# T7BR-Schematic.net
KiCad netlist of a schematic drawn in Altium Designer
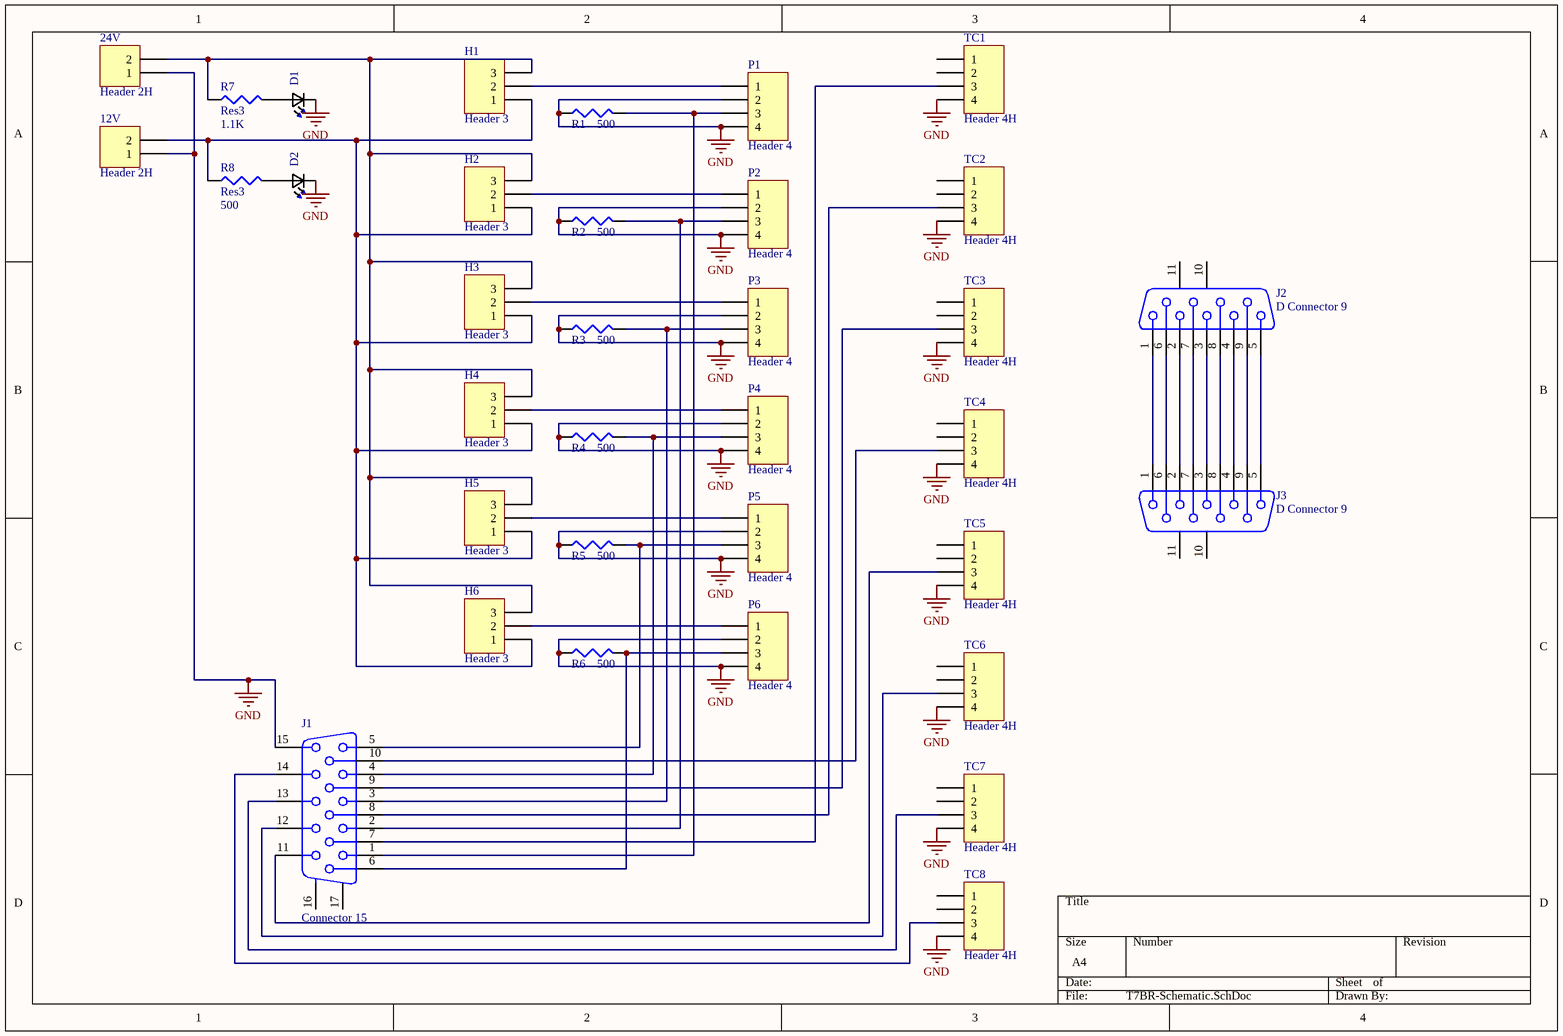
[diagram p0: T7BR-Schematic.SchDoc]

(export (version "E")
  (design (tool "Eeschema 10.0.6"))
  (components
    (comp (ref "12V")
      (value "Header 2H")
      (footprint "WM4900-ND")
      (description "Header, 2-Pin, Right Angle")
      (fields (field (name "PUBLISHER") "Altium Limited"))
      (libsource (lib "Miscellaneous Connectors") (part "Header 2H"))
    )
    (comp (ref "24V")
      (value "Header 2H")
      (footprint "WM4900-ND")
      (description "Header, 2-Pin, Right Angle")
      (fields (field (name "PUBLISHER") "Altium Limited"))
      (libsource (lib "Miscellaneous Connectors") (part "Header 2H"))
    )
    (comp (ref "D1")
      (value "~")
      (footprint "*0603")
      (description "Green 571nm LED Indication - Discrete 2V 0603 _1608 Metric_")
      (fields (field (name "DIGI-KEY_PART_NUMBER") "160-1446-1-ND") (field (name "MP") "LTST-C191KGKT"))
      (libsource (lib "LTST-C191KGKT") (part "LTST-C191KGKT"))
    )
    (comp (ref "D2")
      (value "~")
      (footprint "*0603")
      (description "Green 571nm LED Indication - Discrete 2V 0603 _1608 Metric_")
      (fields (field (name "DIGI-KEY_PART_NUMBER") "160-1446-1-ND") (field (name "MP") "LTST-C191KGKT"))
      (libsource (lib "LTST-C191KGKT") (part "LTST-C191KGKT"))
    )
    (comp (ref "H1")
      (value "Header 3")
      (footprint "HDR1X3")
      (description "Header, 3-Pin")
      (fields (field (name "PUBLISHER") "Altium Limited"))
      (libsource (lib "Miscellaneous Connectors") (part "Header 3"))
    )
    (comp (ref "H2")
      (value "Header 3")
      (footprint "HDR1X3")
      (description "Header, 3-Pin")
      (fields (field (name "PUBLISHER") "Altium Limited"))
      (libsource (lib "Miscellaneous Connectors") (part "Header 3"))
    )
    (comp (ref "H3")
      (value "Header 3")
      (footprint "HDR1X3")
      (description "Header, 3-Pin")
      (fields (field (name "PUBLISHER") "Altium Limited"))
      (libsource (lib "Miscellaneous Connectors") (part "Header 3"))
    )
    (comp (ref "H4")
      (value "Header 3")
      (footprint "HDR1X3")
      (description "Header, 3-Pin")
      (fields (field (name "PUBLISHER") "Altium Limited"))
      (libsource (lib "Miscellaneous Connectors") (part "Header 3"))
    )
    (comp (ref "H5")
      (value "Header 3")
      (footprint "HDR1X3")
      (description "Header, 3-Pin")
      (fields (field (name "PUBLISHER") "Altium Limited"))
      (libsource (lib "Miscellaneous Connectors") (part "Header 3"))
    )
    (comp (ref "H6")
      (value "Header 3")
      (footprint "HDR1X3")
      (description "Header, 3-Pin")
      (fields (field (name "PUBLISHER") "Altium Limited"))
      (libsource (lib "Miscellaneous Connectors") (part "Header 3"))
    )
    (comp (ref "J1")
      (value "Connector 15")
      (footprint "DSUB_15")
      (description "Receptacle Assembly, 15-Pin, Sim Line Connector")
      (fields (field (name "PUBLISHER") "Altium Limited"))
      (libsource (lib "Miscellaneous Connectors") (part "Connector 15"))
    )
    (comp (ref "J2")
      (value "D Connector 9")
      (footprint "DSUB_9")
      (description "Receptacle Assembly, 9 Position, Right Angle")
      (fields (field (name "PUBLISHER") "Altium Limited"))
      (libsource (lib "Miscellaneous Connectors") (part "D Connector 9"))
    )
    (comp (ref "J3")
      (value "D Connector 9")
      (footprint "DSUB_9")
      (description "Receptacle Assembly, 9 Position, Right Angle")
      (fields (field (name "PUBLISHER") "Altium Limited"))
      (libsource (lib "") (part "D Connector 9_1"))
    )
    (comp (ref "P1")
      (value "Header 4")
      (footprint "WM4900-ND-4")
      (description "Header, 4-Pin")
      (fields (field (name "PUBLISHER") "Altium Limited"))
      (libsource (lib "Miscellaneous Connectors") (part "Header 4"))
    )
    (comp (ref "P2")
      (value "Header 4")
      (footprint "WM4900-ND-4")
      (description "Header, 4-Pin")
      (fields (field (name "PUBLISHER") "Altium Limited"))
      (libsource (lib "Miscellaneous Connectors") (part "Header 4"))
    )
    (comp (ref "P3")
      (value "Header 4")
      (footprint "WM4900-ND-4")
      (description "Header, 4-Pin")
      (fields (field (name "PUBLISHER") "Altium Limited"))
      (libsource (lib "Miscellaneous Connectors") (part "Header 4"))
    )
    (comp (ref "P4")
      (value "Header 4")
      (footprint "WM4900-ND-4")
      (description "Header, 4-Pin")
      (fields (field (name "PUBLISHER") "Altium Limited"))
      (libsource (lib "Miscellaneous Connectors") (part "Header 4"))
    )
    (comp (ref "P5")
      (value "Header 4")
      (footprint "WM4900-ND-4")
      (description "Header, 4-Pin")
      (fields (field (name "PUBLISHER") "Altium Limited"))
      (libsource (lib "Miscellaneous Connectors") (part "Header 4"))
    )
    (comp (ref "P6")
      (value "Header 4")
      (footprint "WM4900-ND-4")
      (description "Header, 4-Pin")
      (fields (field (name "PUBLISHER") "Altium Limited"))
      (libsource (lib "Miscellaneous Connectors") (part "Header 4"))
    )
    (comp (ref "R1")
      (value "500")
      (footprint "J1-0603")
      (description "Resistor")
      (fields (field (name "PUBLISHER") "Altium Limited"))
      (libsource (lib "Miscellaneous Devices") (part "Res3"))
    )
    (comp (ref "R2")
      (value "500")
      (footprint "J1-0603")
      (description "Resistor")
      (fields (field (name "PUBLISHER") "Altium Limited"))
      (libsource (lib "Miscellaneous Devices") (part "Res3"))
    )
    (comp (ref "R3")
      (value "500")
      (footprint "J1-0603")
      (description "Resistor")
      (fields (field (name "PUBLISHER") "Altium Limited"))
      (libsource (lib "Miscellaneous Devices") (part "Res3"))
    )
    (comp (ref "R4")
      (value "500")
      (footprint "J1-0603")
      (description "Resistor")
      (fields (field (name "PUBLISHER") "Altium Limited"))
      (libsource (lib "Miscellaneous Devices") (part "Res3"))
    )
    (comp (ref "R5")
      (value "500")
      (footprint "J1-0603")
      (description "Resistor")
      (fields (field (name "PUBLISHER") "Altium Limited"))
      (libsource (lib "Miscellaneous Devices") (part "Res3"))
    )
    (comp (ref "R6")
      (value "500")
      (footprint "J1-0603")
      (description "Resistor")
      (fields (field (name "PUBLISHER") "Altium Limited"))
      (libsource (lib "Miscellaneous Devices") (part "Res3"))
    )
    (comp (ref "R7")
      (value "Res3")
      (footprint "J1-0603")
      (description "Resistor")
      (fields (field (name "ALTIUM_VALUE") "1.1K") (field (name "PUBLISHER") "Altium Limited"))
      (libsource (lib "Miscellaneous Devices") (part "Res3"))
    )
    (comp (ref "R8")
      (value "Res3")
      (footprint "J1-0603")
      (description "Resistor")
      (fields (field (name "ALTIUM_VALUE") "500") (field (name "PUBLISHER") "Altium Limited"))
      (libsource (lib "Miscellaneous Devices") (part "Res3"))
    )
    (comp (ref "TC1")
      (value "Header 4H")
      (footprint "Thermocouple F")
      (description "Header, 4-Pin, Right Angle")
      (fields (field (name "PUBLISHER") "Altium Limited"))
      (libsource (lib "Miscellaneous Connectors") (part "Header 4H"))
    )
    (comp (ref "TC2")
      (value "Header 4H")
      (footprint "Thermocouple F")
      (description "Header, 4-Pin, Right Angle")
      (fields (field (name "PUBLISHER") "Altium Limited"))
      (libsource (lib "Miscellaneous Connectors") (part "Header 4H"))
    )
    (comp (ref "TC3")
      (value "Header 4H")
      (footprint "Thermocouple F")
      (description "Header, 4-Pin, Right Angle")
      (fields (field (name "PUBLISHER") "Altium Limited"))
      (libsource (lib "Miscellaneous Connectors") (part "Header 4H"))
    )
    (comp (ref "TC4")
      (value "Header 4H")
      (footprint "Thermocouple F")
      (description "Header, 4-Pin, Right Angle")
      (fields (field (name "PUBLISHER") "Altium Limited"))
      (libsource (lib "Miscellaneous Connectors") (part "Header 4H"))
    )
    (comp (ref "TC5")
      (value "Header 4H")
      (footprint "Thermocouple F")
      (description "Header, 4-Pin, Right Angle")
      (fields (field (name "PUBLISHER") "Altium Limited"))
      (libsource (lib "Miscellaneous Connectors") (part "Header 4H"))
    )
    (comp (ref "TC6")
      (value "Header 4H")
      (footprint "Thermocouple F")
      (description "Header, 4-Pin, Right Angle")
      (fields (field (name "PUBLISHER") "Altium Limited"))
      (libsource (lib "Miscellaneous Connectors") (part "Header 4H"))
    )
    (comp (ref "TC7")
      (value "Header 4H")
      (footprint "Thermocouple F")
      (description "Header, 4-Pin, Right Angle")
      (fields (field (name "PUBLISHER") "Altium Limited"))
      (libsource (lib "Miscellaneous Connectors") (part "Header 4H"))
    )
    (comp (ref "TC8")
      (value "Header 4H")
      (footprint "Thermocouple F")
      (description "Header, 4-Pin, Right Angle")
      (fields (field (name "PUBLISHER") "Altium Limited"))
      (libsource (lib "Miscellaneous Connectors") (part "Header 4H"))
    )
  )
  (nets
    (net (code "1") (name "GND") (class "Default")
      (node (ref "12V") (pin "1") (pinfunction "1_1") (pintype "passive"))
      (node (ref "24V") (pin "1") (pinfunction "1_1") (pintype "passive"))
      (node (ref "D1") (pin "1") (pinfunction "K2_1") (pintype "passive"))
      (node (ref "D2") (pin "1") (pinfunction "K2_1") (pintype "passive"))
      (node (ref "J1") (pin "15") (pinfunction "15_15") (pintype "passive"))
      (node (ref "P1") (pin "2") (pinfunction "2_2") (pintype "passive"))
      (node (ref "P1") (pin "4") (pinfunction "4_4") (pintype "passive"))
      (node (ref "P2") (pin "2") (pinfunction "2_2") (pintype "passive"))
      (node (ref "P2") (pin "4") (pinfunction "4_4") (pintype "passive"))
      (node (ref "P3") (pin "2") (pinfunction "2_2") (pintype "passive"))
      (node (ref "P3") (pin "4") (pinfunction "4_4") (pintype "passive"))
      (node (ref "P4") (pin "2") (pinfunction "2_2") (pintype "passive"))
      (node (ref "P4") (pin "4") (pinfunction "4_4") (pintype "passive"))
      (node (ref "P5") (pin "2") (pinfunction "2_2") (pintype "passive"))
      (node (ref "P5") (pin "4") (pinfunction "4_4") (pintype "passive"))
      (node (ref "P6") (pin "2") (pinfunction "2_2") (pintype "passive"))
      (node (ref "P6") (pin "4") (pinfunction "4_4") (pintype "passive"))
      (node (ref "R1") (pin "1") (pinfunction "1_1") (pintype "passive"))
      (node (ref "R2") (pin "1") (pinfunction "1_1") (pintype "passive"))
      (node (ref "R3") (pin "1") (pinfunction "1_1") (pintype "passive"))
      (node (ref "R4") (pin "1") (pinfunction "1_1") (pintype "passive"))
      (node (ref "R5") (pin "1") (pinfunction "1_1") (pintype "passive"))
      (node (ref "R6") (pin "1") (pinfunction "1_1") (pintype "passive"))
      (node (ref "TC1") (pin "4") (pinfunction "4_4") (pintype "passive"))
      (node (ref "TC2") (pin "4") (pinfunction "4_4") (pintype "passive"))
      (node (ref "TC3") (pin "4") (pinfunction "4_4") (pintype "passive"))
      (node (ref "TC4") (pin "4") (pinfunction "4_4") (pintype "passive"))
      (node (ref "TC5") (pin "4") (pinfunction "4_4") (pintype "passive"))
      (node (ref "TC6") (pin "4") (pinfunction "4_4") (pintype "passive"))
      (node (ref "TC7") (pin "4") (pinfunction "4_4") (pintype "passive"))
      (node (ref "TC8") (pin "4") (pinfunction "4_4") (pintype "passive"))
    )
    (net (code "2") (name "Net-(12V-Pad2)") (class "Default")
      (node (ref "12V") (pin "2") (pinfunction "2_2") (pintype "passive"))
      (node (ref "H1") (pin "1") (pinfunction "1_1") (pintype "passive"))
      (node (ref "H2") (pin "1") (pinfunction "1_1") (pintype "passive"))
      (node (ref "H3") (pin "1") (pinfunction "1_1") (pintype "passive"))
      (node (ref "H4") (pin "1") (pinfunction "1_1") (pintype "passive"))
      (node (ref "H5") (pin "1") (pinfunction "1_1") (pintype "passive"))
      (node (ref "H6") (pin "1") (pinfunction "1_1") (pintype "passive"))
      (node (ref "R8") (pin "1") (pinfunction "1_1") (pintype "passive"))
    )
    (net (code "3") (name "Net-(24V-Pad2)") (class "Default")
      (node (ref "24V") (pin "2") (pinfunction "2_2") (pintype "passive"))
      (node (ref "H1") (pin "3") (pinfunction "3_3") (pintype "passive"))
      (node (ref "H2") (pin "3") (pinfunction "3_3") (pintype "passive"))
      (node (ref "H3") (pin "3") (pinfunction "3_3") (pintype "passive"))
      (node (ref "H4") (pin "3") (pinfunction "3_3") (pintype "passive"))
      (node (ref "H5") (pin "3") (pinfunction "3_3") (pintype "passive"))
      (node (ref "H6") (pin "3") (pinfunction "3_3") (pintype "passive"))
      (node (ref "R7") (pin "1") (pinfunction "1_1") (pintype "passive"))
    )
    (net (code "4") (name "Net-(D1-A2)") (class "Default")
      (node (ref "D1") (pin "2") (pinfunction "A2_2") (pintype "passive"))
      (node (ref "R7") (pin "2") (pinfunction "2_2") (pintype "passive"))
    )
    (net (code "5") (name "Net-(D2-A2)") (class "Default")
      (node (ref "D2") (pin "2") (pinfunction "A2_2") (pintype "passive"))
      (node (ref "R8") (pin "2") (pinfunction "2_2") (pintype "passive"))
    )
    (net (code "6") (name "Net-(H1-Pad2)") (class "Default")
      (node (ref "H1") (pin "2") (pinfunction "2_2") (pintype "passive"))
      (node (ref "P1") (pin "1") (pinfunction "1_1") (pintype "passive"))
    )
    (net (code "7") (name "Net-(H2-Pad2)") (class "Default")
      (node (ref "H2") (pin "2") (pinfunction "2_2") (pintype "passive"))
      (node (ref "P2") (pin "1") (pinfunction "1_1") (pintype "passive"))
    )
    (net (code "8") (name "Net-(H3-Pad2)") (class "Default")
      (node (ref "H3") (pin "2") (pinfunction "2_2") (pintype "passive"))
      (node (ref "P3") (pin "1") (pinfunction "1_1") (pintype "passive"))
    )
    (net (code "9") (name "Net-(H4-Pad2)") (class "Default")
      (node (ref "H4") (pin "2") (pinfunction "2_2") (pintype "passive"))
      (node (ref "P4") (pin "1") (pinfunction "1_1") (pintype "passive"))
    )
    (net (code "10") (name "Net-(H5-Pad2)") (class "Default")
      (node (ref "H5") (pin "2") (pinfunction "2_2") (pintype "passive"))
      (node (ref "P5") (pin "1") (pinfunction "1_1") (pintype "passive"))
    )
    (net (code "11") (name "Net-(H6-Pad2)") (class "Default")
      (node (ref "H6") (pin "2") (pinfunction "2_2") (pintype "passive"))
      (node (ref "P6") (pin "1") (pinfunction "1_1") (pintype "passive"))
    )
    (net (code "12") (name "Net-(J1-Pad1)") (class "Default")
      (node (ref "J1") (pin "1") (pinfunction "1_1") (pintype "passive"))
      (node (ref "P1") (pin "3") (pinfunction "3_3") (pintype "passive"))
      (node (ref "R1") (pin "2") (pinfunction "2_2") (pintype "passive"))
    )
    (net (code "13") (name "Net-(J1-Pad2)") (class "Default")
      (node (ref "J1") (pin "2") (pinfunction "2_2") (pintype "passive"))
      (node (ref "P2") (pin "3") (pinfunction "3_3") (pintype "passive"))
      (node (ref "R2") (pin "2") (pinfunction "2_2") (pintype "passive"))
    )
    (net (code "14") (name "Net-(J1-Pad3)") (class "Default")
      (node (ref "J1") (pin "3") (pinfunction "3_3") (pintype "passive"))
      (node (ref "P3") (pin "3") (pinfunction "3_3") (pintype "passive"))
      (node (ref "R3") (pin "2") (pinfunction "2_2") (pintype "passive"))
    )
    (net (code "15") (name "Net-(J1-Pad4)") (class "Default")
      (node (ref "J1") (pin "4") (pinfunction "4_4") (pintype "passive"))
      (node (ref "P4") (pin "3") (pinfunction "3_3") (pintype "passive"))
      (node (ref "R4") (pin "2") (pinfunction "2_2") (pintype "passive"))
    )
    (net (code "16") (name "Net-(J1-Pad5)") (class "Default")
      (node (ref "J1") (pin "5") (pinfunction "5_5") (pintype "passive"))
      (node (ref "P5") (pin "3") (pinfunction "3_3") (pintype "passive"))
      (node (ref "R5") (pin "2") (pinfunction "2_2") (pintype "passive"))
    )
    (net (code "17") (name "Net-(J1-Pad6)") (class "Default")
      (node (ref "J1") (pin "6") (pinfunction "6_6") (pintype "passive"))
      (node (ref "P6") (pin "3") (pinfunction "3_3") (pintype "passive"))
      (node (ref "R6") (pin "2") (pinfunction "2_2") (pintype "passive"))
    )
    (net (code "18") (name "Net-(J1-Pad7)") (class "Default")
      (node (ref "J1") (pin "7") (pinfunction "7_7") (pintype "passive"))
      (node (ref "TC1") (pin "3") (pinfunction "3_3") (pintype "passive"))
    )
    (net (code "19") (name "Net-(J1-Pad8)") (class "Default")
      (node (ref "J1") (pin "8") (pinfunction "8_8") (pintype "passive"))
      (node (ref "TC2") (pin "3") (pinfunction "3_3") (pintype "passive"))
    )
    (net (code "20") (name "Net-(J1-Pad9)") (class "Default")
      (node (ref "J1") (pin "9") (pinfunction "9_9") (pintype "passive"))
      (node (ref "TC3") (pin "3") (pinfunction "3_3") (pintype "passive"))
    )
    (net (code "21") (name "Net-(J1-Pad10)") (class "Default")
      (node (ref "J1") (pin "10") (pinfunction "10_10") (pintype "passive"))
      (node (ref "TC4") (pin "3") (pinfunction "3_3") (pintype "passive"))
    )
    (net (code "22") (name "Net-(J1-Pad11)") (class "Default")
      (node (ref "J1") (pin "11") (pinfunction "11_11") (pintype "passive"))
      (node (ref "TC5") (pin "3") (pinfunction "3_3") (pintype "passive"))
    )
    (net (code "23") (name "Net-(J1-Pad12)") (class "Default")
      (node (ref "J1") (pin "12") (pinfunction "12_12") (pintype "passive"))
      (node (ref "TC6") (pin "3") (pinfunction "3_3") (pintype "passive"))
    )
    (net (code "24") (name "Net-(J1-Pad13)") (class "Default")
      (node (ref "J1") (pin "13") (pinfunction "13_13") (pintype "passive"))
      (node (ref "TC7") (pin "3") (pinfunction "3_3") (pintype "passive"))
    )
    (net (code "25") (name "Net-(J1-Pad14)") (class "Default")
      (node (ref "J1") (pin "14") (pinfunction "14_14") (pintype "passive"))
      (node (ref "TC8") (pin "3") (pinfunction "3_3") (pintype "passive"))
    )
    (net (code "26") (name "Net-(J2-Pad1)") (class "Default")
      (node (ref "J2") (pin "1") (pinfunction "1_1") (pintype "passive"))
      (node (ref "J3") (pin "1") (pinfunction "1_1") (pintype "passive"))
    )
    (net (code "27") (name "Net-(J2-Pad2)") (class "Default")
      (node (ref "J2") (pin "2") (pinfunction "2_2") (pintype "passive"))
      (node (ref "J3") (pin "2") (pinfunction "2_2") (pintype "passive"))
    )
    (net (code "28") (name "Net-(J2-Pad3)") (class "Default")
      (node (ref "J2") (pin "3") (pinfunction "3_3") (pintype "passive"))
      (node (ref "J3") (pin "3") (pinfunction "3_3") (pintype "passive"))
    )
    (net (code "29") (name "Net-(J2-Pad4)") (class "Default")
      (node (ref "J2") (pin "4") (pinfunction "4_4") (pintype "passive"))
      (node (ref "J3") (pin "4") (pinfunction "4_4") (pintype "passive"))
    )
    (net (code "30") (name "Net-(J2-Pad5)") (class "Default")
      (node (ref "J2") (pin "5") (pinfunction "5_5") (pintype "passive"))
      (node (ref "J3") (pin "5") (pinfunction "5_5") (pintype "passive"))
    )
    (net (code "31") (name "Net-(J2-Pad6)") (class "Default")
      (node (ref "J2") (pin "6") (pinfunction "6_6") (pintype "passive"))
      (node (ref "J3") (pin "6") (pinfunction "6_6") (pintype "passive"))
    )
    (net (code "32") (name "Net-(J2-Pad7)") (class "Default")
      (node (ref "J2") (pin "7") (pinfunction "7_7") (pintype "passive"))
      (node (ref "J3") (pin "7") (pinfunction "7_7") (pintype "passive"))
    )
    (net (code "33") (name "Net-(J2-Pad8)") (class "Default")
      (node (ref "J2") (pin "8") (pinfunction "8_8") (pintype "passive"))
      (node (ref "J3") (pin "8") (pinfunction "8_8") (pintype "passive"))
    )
    (net (code "34") (name "Net-(J2-Pad9)") (class "Default")
      (node (ref "J2") (pin "9") (pinfunction "9_9") (pintype "passive"))
      (node (ref "J3") (pin "9") (pinfunction "9_9") (pintype "passive"))
    )
    (net (code "35") (name "unconnected-(J1-MH1-Pad16)") (class "Default")
      (node (ref "J1") (pin "16") (pinfunction "MH1_16") (pintype "passive"))
    )
    (net (code "36") (name "unconnected-(J1-MH2-Pad17)") (class "Default")
      (node (ref "J1") (pin "17") (pinfunction "MH2_17") (pintype "passive"))
    )
    (net (code "37") (name "unconnected-(J2-MH1-Pad10)") (class "Default")
      (node (ref "J2") (pin "10") (pinfunction "MH1_10") (pintype "passive"))
    )
    (net (code "38") (name "unconnected-(J2-MH2-Pad11)") (class "Default")
      (node (ref "J2") (pin "11") (pinfunction "MH2_11") (pintype "passive"))
    )
    (net (code "39") (name "unconnected-(J3-MH1-Pad10)") (class "Default")
      (node (ref "J3") (pin "10") (pinfunction "MH1_10") (pintype "passive"))
    )
    (net (code "40") (name "unconnected-(J3-MH2-Pad11)") (class "Default")
      (node (ref "J3") (pin "11") (pinfunction "MH2_11") (pintype "passive"))
    )
    (net (code "41") (name "unconnected-(TC1-Pad1)") (class "Default")
      (node (ref "TC1") (pin "1") (pinfunction "1_1") (pintype "passive"))
    )
    (net (code "42") (name "unconnected-(TC1-Pad2)") (class "Default")
      (node (ref "TC1") (pin "2") (pinfunction "2_2") (pintype "passive"))
    )
    (net (code "43") (name "unconnected-(TC2-Pad1)") (class "Default")
      (node (ref "TC2") (pin "1") (pinfunction "1_1") (pintype "passive"))
    )
    (net (code "44") (name "unconnected-(TC2-Pad2)") (class "Default")
      (node (ref "TC2") (pin "2") (pinfunction "2_2") (pintype "passive"))
    )
    (net (code "45") (name "unconnected-(TC3-Pad1)") (class "Default")
      (node (ref "TC3") (pin "1") (pinfunction "1_1") (pintype "passive"))
    )
    (net (code "46") (name "unconnected-(TC3-Pad2)") (class "Default")
      (node (ref "TC3") (pin "2") (pinfunction "2_2") (pintype "passive"))
    )
    (net (code "47") (name "unconnected-(TC4-Pad1)") (class "Default")
      (node (ref "TC4") (pin "1") (pinfunction "1_1") (pintype "passive"))
    )
    (net (code "48") (name "unconnected-(TC4-Pad2)") (class "Default")
      (node (ref "TC4") (pin "2") (pinfunction "2_2") (pintype "passive"))
    )
    (net (code "49") (name "unconnected-(TC5-Pad1)") (class "Default")
      (node (ref "TC5") (pin "1") (pinfunction "1_1") (pintype "passive"))
    )
    (net (code "50") (name "unconnected-(TC5-Pad2)") (class "Default")
      (node (ref "TC5") (pin "2") (pinfunction "2_2") (pintype "passive"))
    )
    (net (code "51") (name "unconnected-(TC6-Pad1)") (class "Default")
      (node (ref "TC6") (pin "1") (pinfunction "1_1") (pintype "passive"))
    )
    (net (code "52") (name "unconnected-(TC6-Pad2)") (class "Default")
      (node (ref "TC6") (pin "2") (pinfunction "2_2") (pintype "passive"))
    )
    (net (code "53") (name "unconnected-(TC7-Pad1)") (class "Default")
      (node (ref "TC7") (pin "1") (pinfunction "1_1") (pintype "passive"))
    )
    (net (code "54") (name "unconnected-(TC7-Pad2)") (class "Default")
      (node (ref "TC7") (pin "2") (pinfunction "2_2") (pintype "passive"))
    )
    (net (code "55") (name "unconnected-(TC8-Pad1)") (class "Default")
      (node (ref "TC8") (pin "1") (pinfunction "1_1") (pintype "passive"))
    )
    (net (code "56") (name "unconnected-(TC8-Pad2)") (class "Default")
      (node (ref "TC8") (pin "2") (pinfunction "2_2") (pintype "passive"))
    )
  )
)
